# Spectacle_Servo_Control_Board.net
KiCad netlist of a schematic drawn in EAGLE
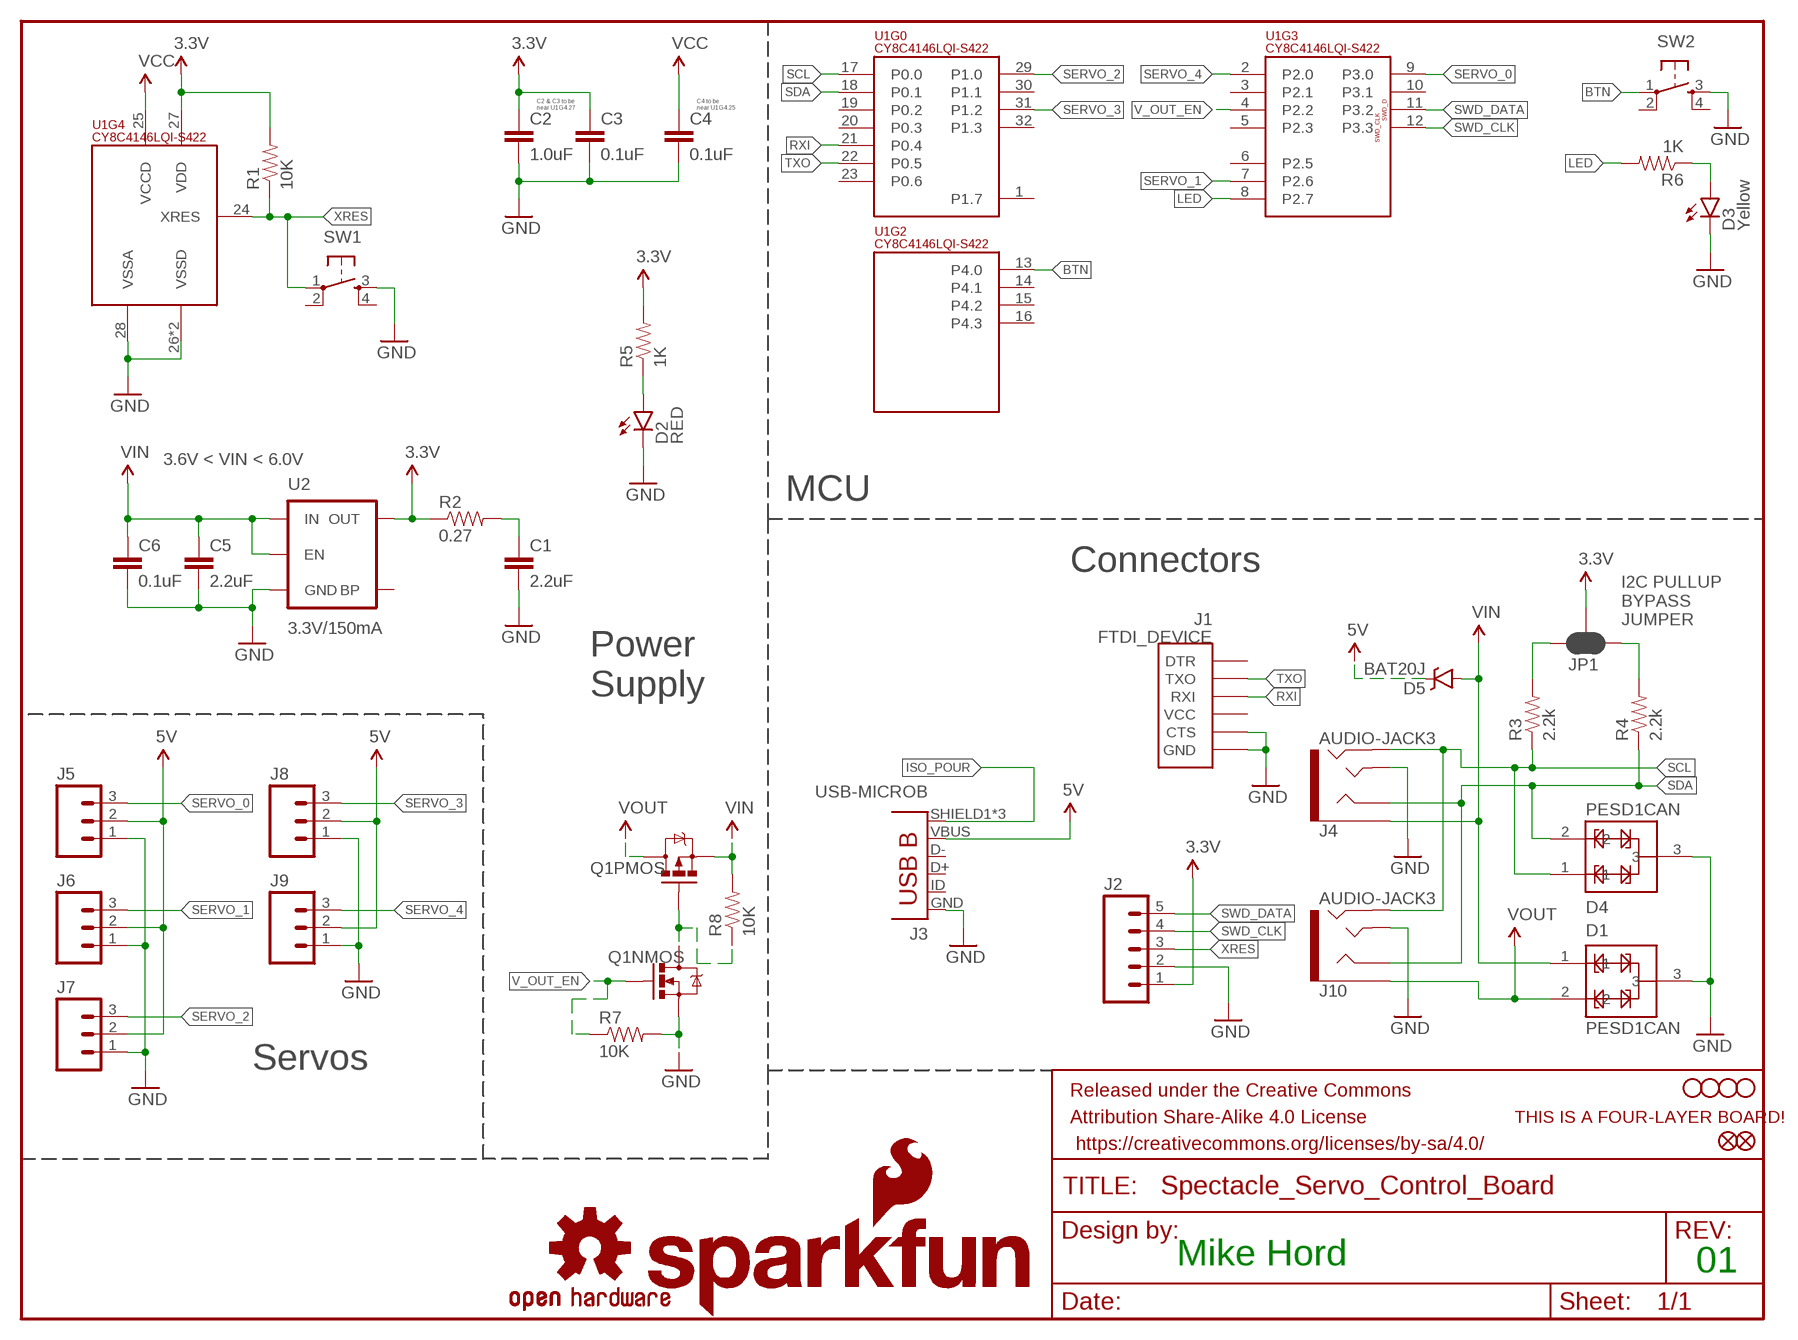
[diagram p0: schematic, sheet 1]

(export (version "E")
  (design (tool "Eeschema 10.0.6"))
  (components
    (comp (ref "C1")
      (value "2.2uF")
      (footprint "eagle-import:0603-CAP")
      (libsource (lib "eagle-import") (part "2.2UF-10V-20%(0603)"))
    )
    (comp (ref "C2")
      (value "1.0uF")
      (footprint "eagle-import:0402-CAP")
      (libsource (lib "eagle-import") (part "1.0UF-16V-10%(0402)"))
    )
    (comp (ref "C3")
      (value "0.1uF")
      (footprint "eagle-import:0402-CAP")
      (libsource (lib "eagle-import") (part "0.1UF-16V(+-10%)(0402)"))
    )
    (comp (ref "C4")
      (value "0.1uF")
      (footprint "eagle-import:0402-CAP")
      (libsource (lib "eagle-import") (part "0.1UF-16V(+-10%)(0402)"))
    )
    (comp (ref "C5")
      (value "2.2uF")
      (footprint "eagle-import:0603-CAP")
      (libsource (lib "eagle-import") (part "2.2UF-10V-20%(0603)"))
    )
    (comp (ref "C6")
      (value "0.1uF")
      (footprint "eagle-import:0402-CAP")
      (libsource (lib "eagle-import") (part "0.1UF-16V(+-10%)(0402)"))
    )
    (comp (ref "D1")
      (value "PESD1CAN")
      (footprint "eagle-import:SOT23-3")
      (libsource (lib "eagle-import") (part "PESD1CAN"))
    )
    (comp (ref "D2")
      (value "RED")
      (footprint "eagle-import:LED-0603")
      (libsource (lib "eagle-import") (part "LED-RED0603"))
    )
    (comp (ref "D3")
      (value "Yellow")
      (footprint "eagle-import:LED-0603")
      (libsource (lib "eagle-import") (part "LED-YELLOW0603-SMART"))
    )
    (comp (ref "D4")
      (value "PESD1CAN")
      (footprint "eagle-import:SOT23-3")
      (libsource (lib "eagle-import") (part "PESD1CAN"))
    )
    (comp (ref "D5")
      (value "BAT20J")
      (footprint "eagle-import:SOD-323")
      (libsource (lib "eagle-import") (part "DIODE-SCHOTTKY-BAT20J"))
    )
    (comp (ref "FD1")
      (value "FIDUCIALUFIDUCIAL")
      (footprint "eagle-import:MICRO-FIDUCIAL")
      (libsource (lib "eagle-import") (part "FIDUCIALUFIDUCIAL"))
    )
    (comp (ref "FD2")
      (value "FIDUCIALUFIDUCIAL")
      (footprint "eagle-import:MICRO-FIDUCIAL")
      (libsource (lib "eagle-import") (part "FIDUCIALUFIDUCIAL"))
    )
    (comp (ref "FRAME1")
      (value "FRAME-LETTER")
      (footprint "eagle-import:CREATIVE_COMMONS")
      (libsource (lib "eagle-import") (part "FRAME-LETTER"))
    )
    (comp (ref "H1")
      (value "STAND-OFF")
      (footprint "eagle-import:STAND-OFF")
      (libsource (lib "eagle-import") (part "STAND-OFF"))
    )
    (comp (ref "H2")
      (value "STAND-OFF")
      (footprint "eagle-import:STAND-OFF")
      (libsource (lib "eagle-import") (part "STAND-OFF"))
    )
    (comp (ref "H3")
      (value "STAND-OFF")
      (footprint "eagle-import:STAND-OFF")
      (libsource (lib "eagle-import") (part "STAND-OFF"))
    )
    (comp (ref "H4")
      (value "STAND-OFF")
      (footprint "eagle-import:STAND-OFF")
      (libsource (lib "eagle-import") (part "STAND-OFF"))
    )
    (comp (ref "J1")
      (value "FTDI_DEVICE")
      (footprint "eagle-import:FTDI_DEVICE_SIDE")
      (libsource (lib "eagle-import") (part "FTDI_DEVICE"))
    )
    (comp (ref "J2")
      (value "M05PTH")
      (footprint "eagle-import:1X05")
      (libsource (lib "eagle-import") (part "M05PTH"))
    )
    (comp (ref "J3")
      (value "USB-MICROB")
      (footprint "eagle-import:USB-B-MICRO-SMD_V03")
      (libsource (lib "eagle-import") (part "USB-MICROB{dblquote}"))
    )
    (comp (ref "J4")
      (value "AUDIO-JACK3")
      (footprint "eagle-import:AUDIO-JACK-TRRS-SMD")
      (libsource (lib "eagle-import") (part "AUDIO-JACK3"))
    )
    (comp (ref "J5")
      (value "M03LOCK")
      (footprint "eagle-import:1X03_LOCK")
      (libsource (lib "eagle-import") (part "M03LOCK"))
    )
    (comp (ref "J6")
      (value "M03LOCK")
      (footprint "eagle-import:1X03_LOCK")
      (libsource (lib "eagle-import") (part "M03LOCK"))
    )
    (comp (ref "J7")
      (value "M03LOCK")
      (footprint "eagle-import:1X03_LOCK")
      (libsource (lib "eagle-import") (part "M03LOCK"))
    )
    (comp (ref "J8")
      (value "M03LOCK")
      (footprint "eagle-import:1X03_LOCK")
      (libsource (lib "eagle-import") (part "M03LOCK"))
    )
    (comp (ref "J9")
      (value "M03LOCK")
      (footprint "eagle-import:1X03_LOCK")
      (libsource (lib "eagle-import") (part "M03LOCK"))
    )
    (comp (ref "J10")
      (value "AUDIO-JACK3")
      (footprint "eagle-import:AUDIO-JACK-TRRS-SMD")
      (libsource (lib "eagle-import") (part "AUDIO-JACK3"))
    )
    (comp (ref "JP1")
      (value "JUMPER-PAD-3-NC_BY_PASTE")
      (footprint "eagle-import:PAD-JUMPER-3-NC_BY_PASTE_YES_SILK_FULL_BOX")
      (libsource (lib "eagle-import") (part "JUMPER-PAD-3-NC_BY_PASTE"))
    )
    (comp (ref "LOGO1")
      (value "OSHW-LOGOS")
      (footprint "eagle-import:OSHW-LOGO-S")
      (libsource (lib "eagle-import") (part "OSHW-LOGOS"))
    )
    (comp (ref "LOGO2")
      (value "SFE_LOGO_NAME_FLAME.1_INCH")
      (footprint "eagle-import:SFE_LOGO_NAME_FLAME_.1")
      (libsource (lib "eagle-import") (part "SFE_LOGO_NAME_FLAME.1_INCH"))
    )
    (comp (ref "LOGO3")
      (value "SFE_LOGO_NAME_FLAME.1_INCH")
      (footprint "eagle-import:SFE_LOGO_NAME_FLAME_.1")
      (libsource (lib "eagle-import") (part "SFE_LOGO_NAME_FLAME.1_INCH"))
    )
    (comp (ref "LOGO4")
      (value "OSHW-LOGOS")
      (footprint "eagle-import:OSHW-LOGO-S")
      (libsource (lib "eagle-import") (part "OSHW-LOGOS"))
    )
    (comp (ref "Q1")
      (value "IRF7509")
      (footprint "eagle-import:MSOP8")
      (libsource (lib "eagle-import") (part "IRF7509"))
    )
    (comp (ref "R1")
      (value "10K")
      (footprint "eagle-import:0603-RES")
      (libsource (lib "eagle-import") (part "10KOHM-1/10W-1%(0603)0603"))
    )
    (comp (ref "R2")
      (value "0.27")
      (footprint "eagle-import:0603-RES")
      (libsource (lib "eagle-import") (part "0.27OHM-1/10W-1%(0603)"))
    )
    (comp (ref "R3")
      (value "2.2k")
      (footprint "eagle-import:0603-RES")
      (libsource (lib "eagle-import") (part "2.2KOHM-1/10W-1%(0603)"))
    )
    (comp (ref "R4")
      (value "2.2k")
      (footprint "eagle-import:0603-RES")
      (libsource (lib "eagle-import") (part "2.2KOHM-1/10W-1%(0603)"))
    )
    (comp (ref "R5")
      (value "1K")
      (footprint "eagle-import:0603-RES")
      (libsource (lib "eagle-import") (part "1KOHM-1/10W-1%(0603)"))
    )
    (comp (ref "R6")
      (value "1K")
      (footprint "eagle-import:0603-RES")
      (libsource (lib "eagle-import") (part "1KOHM-1/10W-1%(0603)"))
    )
    (comp (ref "R7")
      (value "10K")
      (footprint "eagle-import:0603-RES")
      (libsource (lib "eagle-import") (part "10KOHM-1/10W-1%(0603)0603"))
    )
    (comp (ref "R8")
      (value "10K")
      (footprint "eagle-import:0603-RES")
      (libsource (lib "eagle-import") (part "10KOHM-1/10W-1%(0603)0603"))
    )
    (comp (ref "SW1")
      (value "SWITCH_SPST_4_PINRECT")
      (footprint "eagle-import:TACTILE_SWITCH_SMD_4.6X2.8MM")
      (libsource (lib "eagle-import") (part "SWITCH_SPST_4_PINRECT"))
    )
    (comp (ref "SW2")
      (value "SWITCH_SPST_4_PINRECT")
      (footprint "eagle-import:TACTILE_SWITCH_SMD_4.6X2.8MM")
      (libsource (lib "eagle-import") (part "SWITCH_SPST_4_PINRECT"))
    )
    (comp (ref "U$1")
      (value "FOUR_LAYER_WARNING")
      (footprint "eagle-import:FOUR_LAYER_WARNING")
      (libsource (lib "eagle-import") (part "FOUR_LAYER_WARNING"))
    )
    (comp (ref "U1")
      (value "CY8C4146LQI-S422")
      (footprint "eagle-import:QFN-32")
      (libsource (lib "eagle-import") (part "PSOC4_4100S_32QFN"))
    )
    (comp (ref "U2")
      (value "3.3V/150mA")
      (footprint "eagle-import:SOT23-5")
      (libsource (lib "eagle-import") (part "V_REG_MIC52053.3V"))
    )
  )
  (nets
    (net (code "1") (name "3.3V") (class "Default")
      (node (ref "C2") (pin "1") (pinfunction "1_1") (pintype "passive"))
      (node (ref "C3") (pin "1") (pinfunction "1_1") (pintype "passive"))
      (node (ref "J2") (pin "1") (pinfunction "1_1") (pintype "passive"))
      (node (ref "JP1") (pin "2") (pinfunction "2_2") (pintype "passive"))
      (node (ref "R1") (pin "2") (pinfunction "2_2") (pintype "passive"))
      (node (ref "R2") (pin "1") (pinfunction "1_1") (pintype "passive"))
      (node (ref "R5") (pin "2") (pinfunction "2_2") (pintype "passive"))
      (node (ref "U1") (pin "27") (pinfunction "VDD_27") (pintype "bidirectional"))
      (node (ref "U2") (pin "5") (pinfunction "OUT_5") (pintype "passive"))
    )
    (net (code "2") (name "5V") (class "Default")
      (node (ref "D5") (pin "C") (pinfunction "C_C") (pintype "passive"))
      (node (ref "J3") (pin "VBUS") (pinfunction "VBUS_VBUS") (pintype "bidirectional"))
      (node (ref "J5") (pin "2") (pinfunction "2_2") (pintype "passive"))
      (node (ref "J6") (pin "2") (pinfunction "2_2") (pintype "passive"))
      (node (ref "J7") (pin "2") (pinfunction "2_2") (pintype "passive"))
      (node (ref "J8") (pin "2") (pinfunction "2_2") (pintype "passive"))
      (node (ref "J9") (pin "2") (pinfunction "2_2") (pintype "passive"))
    )
    (net (code "3") (name "BTN") (class "Default")
      (node (ref "SW2") (pin "1") (pinfunction "1_1") (pintype "passive"))
      (node (ref "U1") (pin "13") (pinfunction "P4.0_13") (pintype "bidirectional"))
    )
    (net (code "4") (name "GND") (class "Default")
      (node (ref "C1") (pin "2") (pinfunction "2_2") (pintype "passive"))
      (node (ref "C2") (pin "2") (pinfunction "2_2") (pintype "passive"))
      (node (ref "C3") (pin "2") (pinfunction "2_2") (pintype "passive"))
      (node (ref "C4") (pin "2") (pinfunction "2_2") (pintype "passive"))
      (node (ref "C5") (pin "2") (pinfunction "2_2") (pintype "passive"))
      (node (ref "C6") (pin "2") (pinfunction "2_2") (pintype "passive"))
      (node (ref "D1") (pin "3") (pinfunction "3_3") (pintype "bidirectional"))
      (node (ref "D2") (pin "C") (pinfunction "C_C") (pintype "passive"))
      (node (ref "D3") (pin "C") (pinfunction "C_C") (pintype "passive"))
      (node (ref "D4") (pin "3") (pinfunction "3_3") (pintype "bidirectional"))
      (node (ref "J1") (pin "P$5") (pinfunction "CTS_P$5") (pintype "bidirectional"))
      (node (ref "J1") (pin "P$6") (pinfunction "GND_P$6") (pintype "bidirectional"))
      (node (ref "J10") (pin "TIP") (pinfunction "TIP_TIP") (pintype "bidirectional"))
      (node (ref "J2") (pin "2") (pinfunction "2_2") (pintype "passive"))
      (node (ref "J3") (pin "GND") (pinfunction "GND_GND") (pintype "bidirectional"))
      (node (ref "J4") (pin "TIP") (pinfunction "TIP_TIP") (pintype "bidirectional"))
      (node (ref "J5") (pin "1") (pinfunction "1_1") (pintype "passive"))
      (node (ref "J6") (pin "1") (pinfunction "1_1") (pintype "passive"))
      (node (ref "J7") (pin "1") (pinfunction "1_1") (pintype "passive"))
      (node (ref "J8") (pin "1") (pinfunction "1_1") (pintype "passive"))
      (node (ref "J9") (pin "1") (pinfunction "1_1") (pintype "passive"))
      (node (ref "Q1") (pin "1") (pinfunction "S_1") (pintype "passive"))
      (node (ref "R7") (pin "2") (pinfunction "2_2") (pintype "passive"))
      (node (ref "SW1") (pin "3") (pinfunction "3_3") (pintype "passive"))
      (node (ref "SW2") (pin "3") (pinfunction "3_3") (pintype "passive"))
      (node (ref "U1") (pin "26") (pinfunction "VSSD_26") (pintype "bidirectional"))
      (node (ref "U1") (pin "28") (pinfunction "VSSA_28") (pintype "bidirectional"))
      (node (ref "U1") (pin "EP") (pinfunction "VSSD_EP") (pintype "bidirectional"))
      (node (ref "U2") (pin "2") (pinfunction "GND_2") (pintype "input"))
    )
    (net (code "5") (name "ISO_POUR") (class "Default")
      (node (ref "J3") (pin "SHIELD1") (pinfunction "SHIELD_SHIELD1") (pintype "bidirectional"))
      (node (ref "J3") (pin "SHIELD2") (pinfunction "SHIELD_SHIELD2") (pintype "bidirectional"))
      (node (ref "J3") (pin "SHIELD3") (pinfunction "SHIELD_SHIELD3") (pintype "bidirectional"))
    )
    (net (code "6") (name "LED") (class "Default")
      (node (ref "R6") (pin "2") (pinfunction "2_2") (pintype "passive"))
      (node (ref "U1") (pin "8") (pinfunction "P2.7_8") (pintype "bidirectional"))
    )
    (net (code "7") (name "Net-(C1-Pad1)") (class "Default")
      (node (ref "C1") (pin "1") (pinfunction "1_1") (pintype "passive"))
      (node (ref "R2") (pin "2") (pinfunction "2_2") (pintype "passive"))
    )
    (net (code "8") (name "Net-(D2-PadA)") (class "Default")
      (node (ref "D2") (pin "A") (pinfunction "A_A") (pintype "passive"))
      (node (ref "R5") (pin "1") (pinfunction "1_1") (pintype "passive"))
    )
    (net (code "9") (name "Net-(D3-PadA)") (class "Default")
      (node (ref "D3") (pin "A") (pinfunction "A_A") (pintype "passive"))
      (node (ref "R6") (pin "1") (pinfunction "1_1") (pintype "passive"))
    )
    (net (code "10") (name "Net-(JP1-Pad1)") (class "Default")
      (node (ref "JP1") (pin "1") (pinfunction "1_1") (pintype "passive"))
      (node (ref "R4") (pin "2") (pinfunction "2_2") (pintype "passive"))
    )
    (net (code "11") (name "Net-(JP1-Pad3)") (class "Default")
      (node (ref "JP1") (pin "3") (pinfunction "3_3") (pintype "passive"))
      (node (ref "R3") (pin "2") (pinfunction "2_2") (pintype "passive"))
    )
    (net (code "12") (name "Net-(Q1B-G)") (class "Default")
      (node (ref "Q1") (pin "4") (pinfunction "G_4") (pintype "passive"))
      (node (ref "Q1") (pin "7") (pinfunction "D_7") (pintype "passive"))
      (node (ref "Q1") (pin "8") (pinfunction "D_8") (pintype "passive"))
      (node (ref "R8") (pin "1") (pinfunction "1_1") (pintype "passive"))
    )
    (net (code "13") (name "RXI") (class "Default")
      (node (ref "J1") (pin "P$3") (pinfunction "RXI_P$3") (pintype "bidirectional"))
      (node (ref "U1") (pin "21") (pinfunction "P0.4_21") (pintype "bidirectional"))
    )
    (net (code "14") (name "SCL") (class "Default")
      (node (ref "D4") (pin "1") (pinfunction "1_1") (pintype "bidirectional"))
      (node (ref "J10") (pin "RING2") (pinfunction "RING2_RING2") (pintype "bidirectional"))
      (node (ref "J4") (pin "RING2") (pinfunction "RING2_RING2") (pintype "bidirectional"))
      (node (ref "R3") (pin "1") (pinfunction "1_1") (pintype "passive"))
      (node (ref "U1") (pin "17") (pinfunction "P0.0_17") (pintype "bidirectional"))
    )
    (net (code "15") (name "SDA") (class "Default")
      (node (ref "D4") (pin "2") (pinfunction "2_2") (pintype "bidirectional"))
      (node (ref "J10") (pin "RING1") (pinfunction "RING1_RING1") (pintype "bidirectional"))
      (node (ref "J4") (pin "RING1") (pinfunction "RING1_RING1") (pintype "bidirectional"))
      (node (ref "R4") (pin "1") (pinfunction "1_1") (pintype "passive"))
      (node (ref "U1") (pin "18") (pinfunction "P0.1_18") (pintype "bidirectional"))
    )
    (net (code "16") (name "SERVO_0") (class "Default")
      (node (ref "J5") (pin "3") (pinfunction "3_3") (pintype "passive"))
      (node (ref "U1") (pin "9") (pinfunction "P3.0_9") (pintype "bidirectional"))
    )
    (net (code "17") (name "SERVO_1") (class "Default")
      (node (ref "J6") (pin "3") (pinfunction "3_3") (pintype "passive"))
      (node (ref "U1") (pin "7") (pinfunction "P2.6_7") (pintype "bidirectional"))
    )
    (net (code "18") (name "SERVO_2") (class "Default")
      (node (ref "J7") (pin "3") (pinfunction "3_3") (pintype "passive"))
      (node (ref "U1") (pin "29") (pinfunction "P1.0_29") (pintype "bidirectional"))
    )
    (net (code "19") (name "SERVO_3") (class "Default")
      (node (ref "J8") (pin "3") (pinfunction "3_3") (pintype "passive"))
      (node (ref "U1") (pin "31") (pinfunction "P1.2_31") (pintype "bidirectional"))
    )
    (net (code "20") (name "SERVO_4") (class "Default")
      (node (ref "J9") (pin "3") (pinfunction "3_3") (pintype "passive"))
      (node (ref "U1") (pin "2") (pinfunction "P2.0_2") (pintype "bidirectional"))
    )
    (net (code "21") (name "SWD_CLK") (class "Default")
      (node (ref "J2") (pin "4") (pinfunction "4_4") (pintype "passive"))
      (node (ref "U1") (pin "12") (pinfunction "P3.3_12") (pintype "bidirectional"))
    )
    (net (code "22") (name "SWD_DATA") (class "Default")
      (node (ref "J2") (pin "5") (pinfunction "5_5") (pintype "passive"))
      (node (ref "U1") (pin "11") (pinfunction "P3.2_11") (pintype "bidirectional"))
    )
    (net (code "23") (name "TXO") (class "Default")
      (node (ref "J1") (pin "P$2") (pinfunction "TXO_P$2") (pintype "bidirectional"))
      (node (ref "U1") (pin "22") (pinfunction "P0.5_22") (pintype "bidirectional"))
    )
    (net (code "24") (name "VCC") (class "Default")
      (node (ref "C4") (pin "1") (pinfunction "1_1") (pintype "passive"))
      (node (ref "U1") (pin "25") (pinfunction "VCCD_25") (pintype "bidirectional"))
    )
    (net (code "25") (name "VIN") (class "Default")
      (node (ref "C5") (pin "1") (pinfunction "1_1") (pintype "passive"))
      (node (ref "C6") (pin "1") (pinfunction "1_1") (pintype "passive"))
      (node (ref "D1") (pin "1") (pinfunction "1_1") (pintype "bidirectional"))
      (node (ref "D5") (pin "A") (pinfunction "A_A") (pintype "passive"))
      (node (ref "J4") (pin "EARTH") (pinfunction "EARTH_EARTH") (pintype "bidirectional"))
      (node (ref "Q1") (pin "3") (pinfunction "S_3") (pintype "passive"))
      (node (ref "R8") (pin "2") (pinfunction "2_2") (pintype "passive"))
      (node (ref "U2") (pin "1") (pinfunction "IN_1") (pintype "input"))
      (node (ref "U2") (pin "3") (pinfunction "EN_3") (pintype "input"))
    )
    (net (code "26") (name "VOUT") (class "Default")
      (node (ref "D1") (pin "2") (pinfunction "2_2") (pintype "bidirectional"))
      (node (ref "J10") (pin "EARTH") (pinfunction "EARTH_EARTH") (pintype "bidirectional"))
      (node (ref "Q1") (pin "5") (pinfunction "D_5") (pintype "passive"))
      (node (ref "Q1") (pin "6") (pinfunction "D_6") (pintype "passive"))
    )
    (net (code "27") (name "V_OUT_EN") (class "Default")
      (node (ref "Q1") (pin "2") (pinfunction "G_2") (pintype "passive"))
      (node (ref "R7") (pin "1") (pinfunction "1_1") (pintype "passive"))
      (node (ref "U1") (pin "4") (pinfunction "P2.2_4") (pintype "bidirectional"))
    )
    (net (code "28") (name "XRES") (class "Default")
      (node (ref "J2") (pin "3") (pinfunction "3_3") (pintype "passive"))
      (node (ref "R1") (pin "1") (pinfunction "1_1") (pintype "passive"))
      (node (ref "SW1") (pin "1") (pinfunction "1_1") (pintype "passive"))
      (node (ref "U1") (pin "24") (pinfunction "XRES_24") (pintype "bidirectional"))
    )
    (net (code "29") (name "unconnected-(J1-DTR-PadP$1)") (class "Default")
      (node (ref "J1") (pin "P$1") (pinfunction "DTR_P$1") (pintype "bidirectional"))
    )
    (net (code "30") (name "unconnected-(J1-VCC-PadP$4)") (class "Default")
      (node (ref "J1") (pin "P$4") (pinfunction "VCC_P$4") (pintype "bidirectional"))
    )
    (net (code "31") (name "unconnected-(J3-PadD+)") (class "Default")
      (node (ref "J3") (pin "D+") (pinfunction "D+_D+") (pintype "bidirectional"))
    )
    (net (code "32") (name "unconnected-(J3-PadD-)") (class "Default")
      (node (ref "J3") (pin "D-") (pinfunction "D-_D-") (pintype "bidirectional"))
    )
    (net (code "33") (name "unconnected-(J3-USBID-PadID)") (class "Default")
      (node (ref "J3") (pin "ID") (pinfunction "USBID_ID") (pintype "bidirectional"))
    )
    (net (code "34") (name "unconnected-(SW1-Pad2)") (class "Default")
      (node (ref "SW1") (pin "2") (pinfunction "2_2") (pintype "passive"))
    )
    (net (code "35") (name "unconnected-(SW1-Pad4)") (class "Default")
      (node (ref "SW1") (pin "4") (pinfunction "4_4") (pintype "passive"))
    )
    (net (code "36") (name "unconnected-(SW2-Pad2)") (class "Default")
      (node (ref "SW2") (pin "2") (pinfunction "2_2") (pintype "passive"))
    )
    (net (code "37") (name "unconnected-(SW2-Pad4)") (class "Default")
      (node (ref "SW2") (pin "4") (pinfunction "4_4") (pintype "passive"))
    )
    (net (code "38") (name "unconnected-(U1A-P0.2-Pad19)") (class "Default")
      (node (ref "U1") (pin "19") (pinfunction "P0.2_19") (pintype "bidirectional"))
    )
    (net (code "39") (name "unconnected-(U1A-P0.3-Pad20)") (class "Default")
      (node (ref "U1") (pin "20") (pinfunction "P0.3_20") (pintype "bidirectional"))
    )
    (net (code "40") (name "unconnected-(U1A-P0.6-Pad23)") (class "Default")
      (node (ref "U1") (pin "23") (pinfunction "P0.6_23") (pintype "bidirectional"))
    )
    (net (code "41") (name "unconnected-(U1A-P1.1-Pad30)") (class "Default")
      (node (ref "U1") (pin "30") (pinfunction "P1.1_30") (pintype "bidirectional"))
    )
    (net (code "42") (name "unconnected-(U1A-P1.3-Pad32)") (class "Default")
      (node (ref "U1") (pin "32") (pinfunction "P1.3_32") (pintype "bidirectional"))
    )
    (net (code "43") (name "unconnected-(U1A-P1.7-Pad1)") (class "Default")
      (node (ref "U1") (pin "1") (pinfunction "P1.7_1") (pintype "bidirectional"))
    )
    (net (code "44") (name "unconnected-(U1B-P4.1-Pad14)") (class "Default")
      (node (ref "U1") (pin "14") (pinfunction "P4.1_14") (pintype "bidirectional"))
    )
    (net (code "45") (name "unconnected-(U1B-P4.2-Pad15)") (class "Default")
      (node (ref "U1") (pin "15") (pinfunction "P4.2_15") (pintype "bidirectional"))
    )
    (net (code "46") (name "unconnected-(U1B-P4.3-Pad16)") (class "Default")
      (node (ref "U1") (pin "16") (pinfunction "P4.3_16") (pintype "bidirectional"))
    )
    (net (code "47") (name "unconnected-(U1C-P2.1-Pad3)") (class "Default")
      (node (ref "U1") (pin "3") (pinfunction "P2.1_3") (pintype "bidirectional"))
    )
    (net (code "48") (name "unconnected-(U1C-P2.3-Pad5)") (class "Default")
      (node (ref "U1") (pin "5") (pinfunction "P2.3_5") (pintype "bidirectional"))
    )
    (net (code "49") (name "unconnected-(U1C-P2.5-Pad6)") (class "Default")
      (node (ref "U1") (pin "6") (pinfunction "P2.5_6") (pintype "bidirectional"))
    )
    (net (code "50") (name "unconnected-(U1C-P3.1-Pad10)") (class "Default")
      (node (ref "U1") (pin "10") (pinfunction "P3.1_10") (pintype "bidirectional"))
    )
    (net (code "51") (name "unconnected-(U2-BP-Pad4)") (class "Default")
      (node (ref "U2") (pin "4") (pinfunction "BP_4") (pintype "input"))
    )
  )
)
